# EL-100-020-030-AnalogOUT.net
KiCad netlist of a schematic drawn in EAGLE
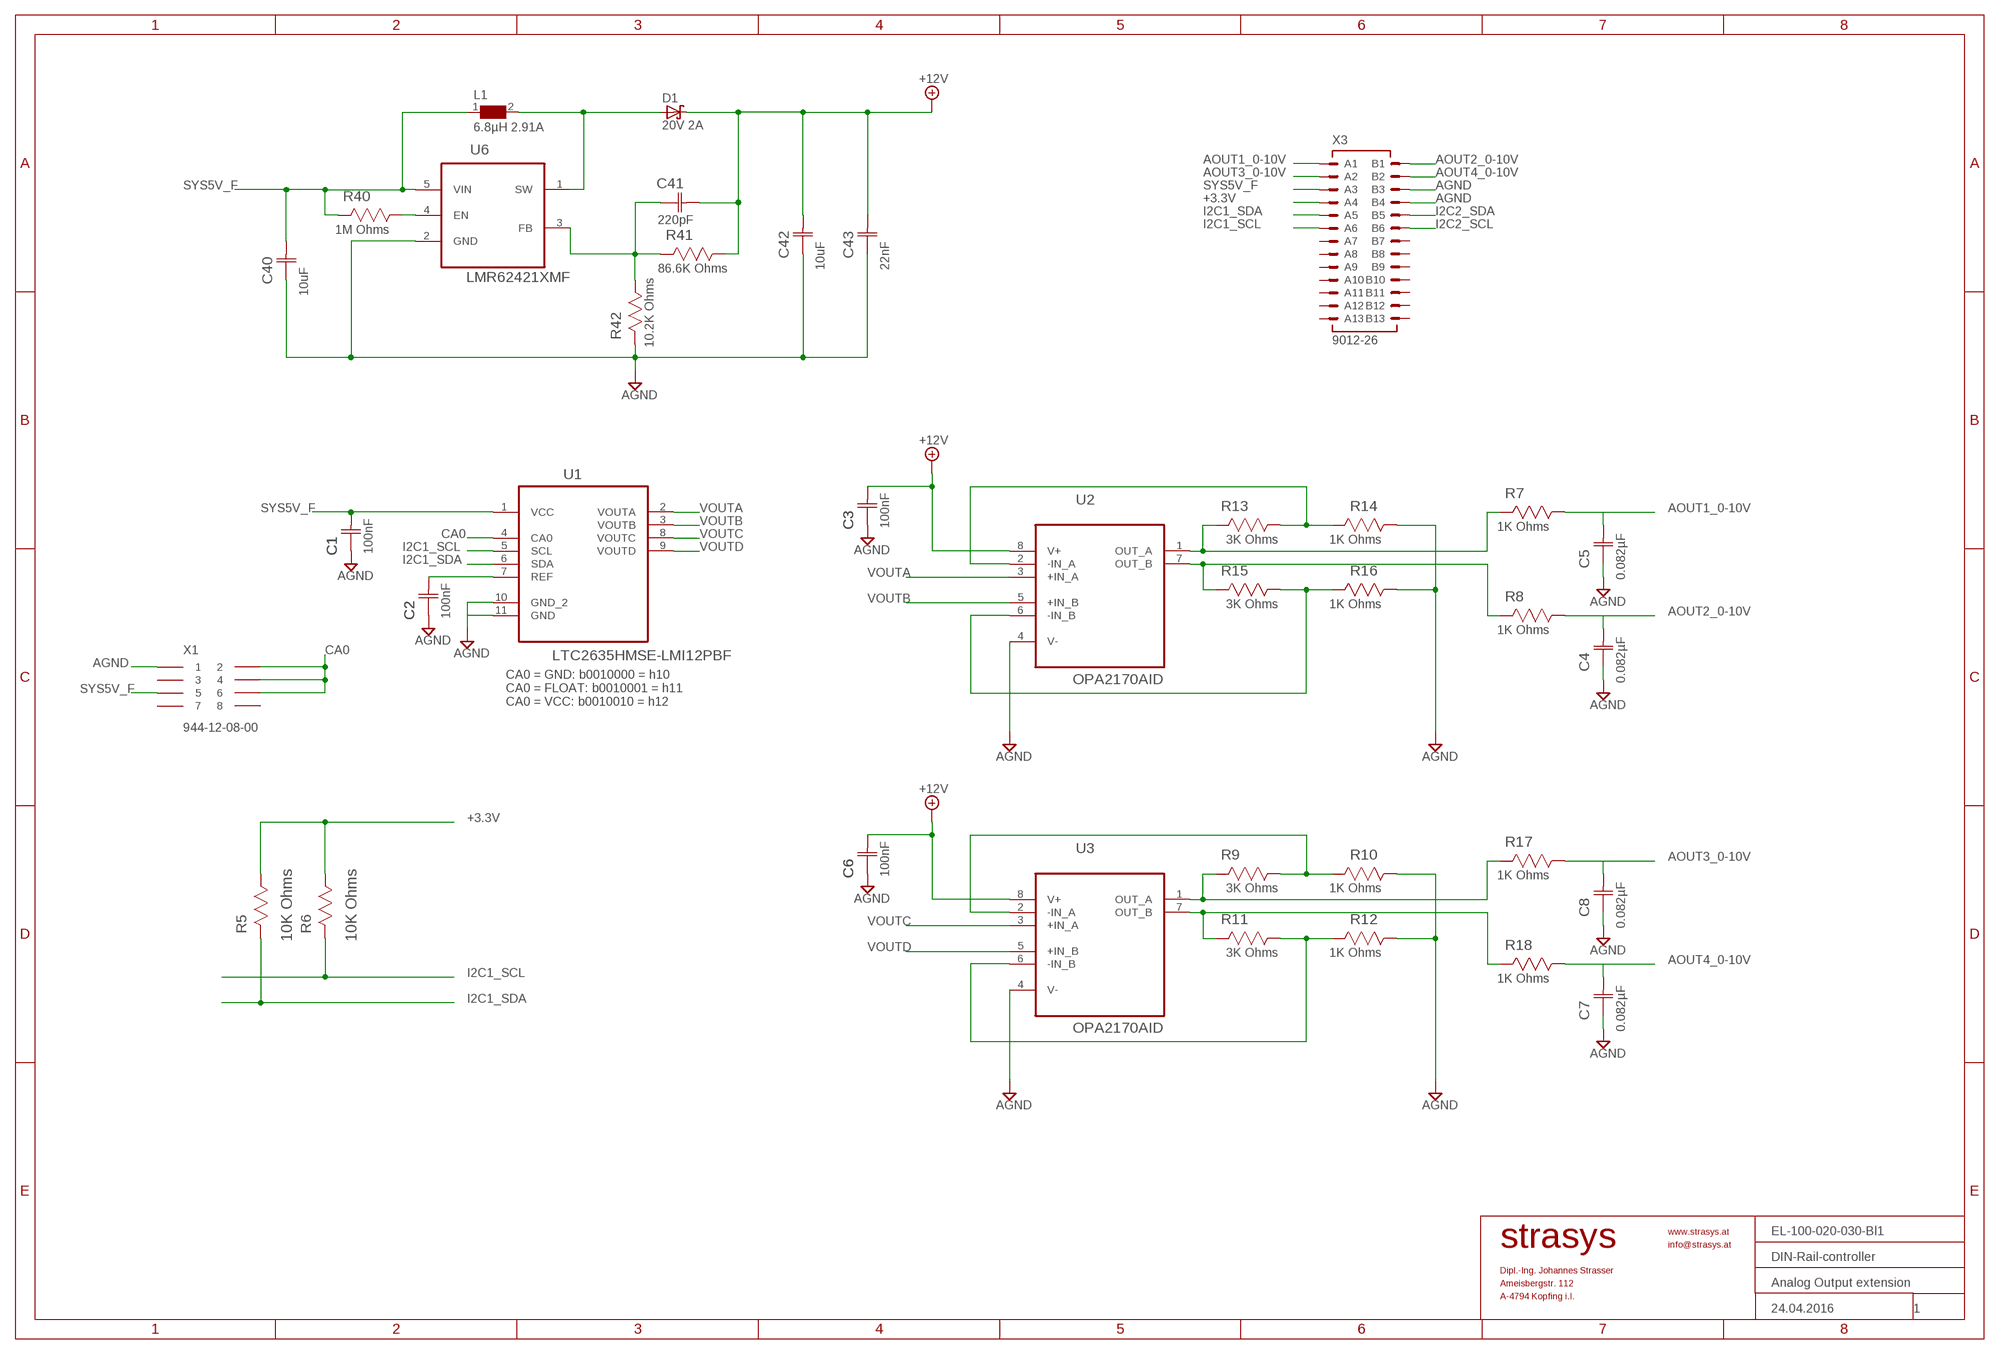
[diagram p0: schematic, sheet 1]
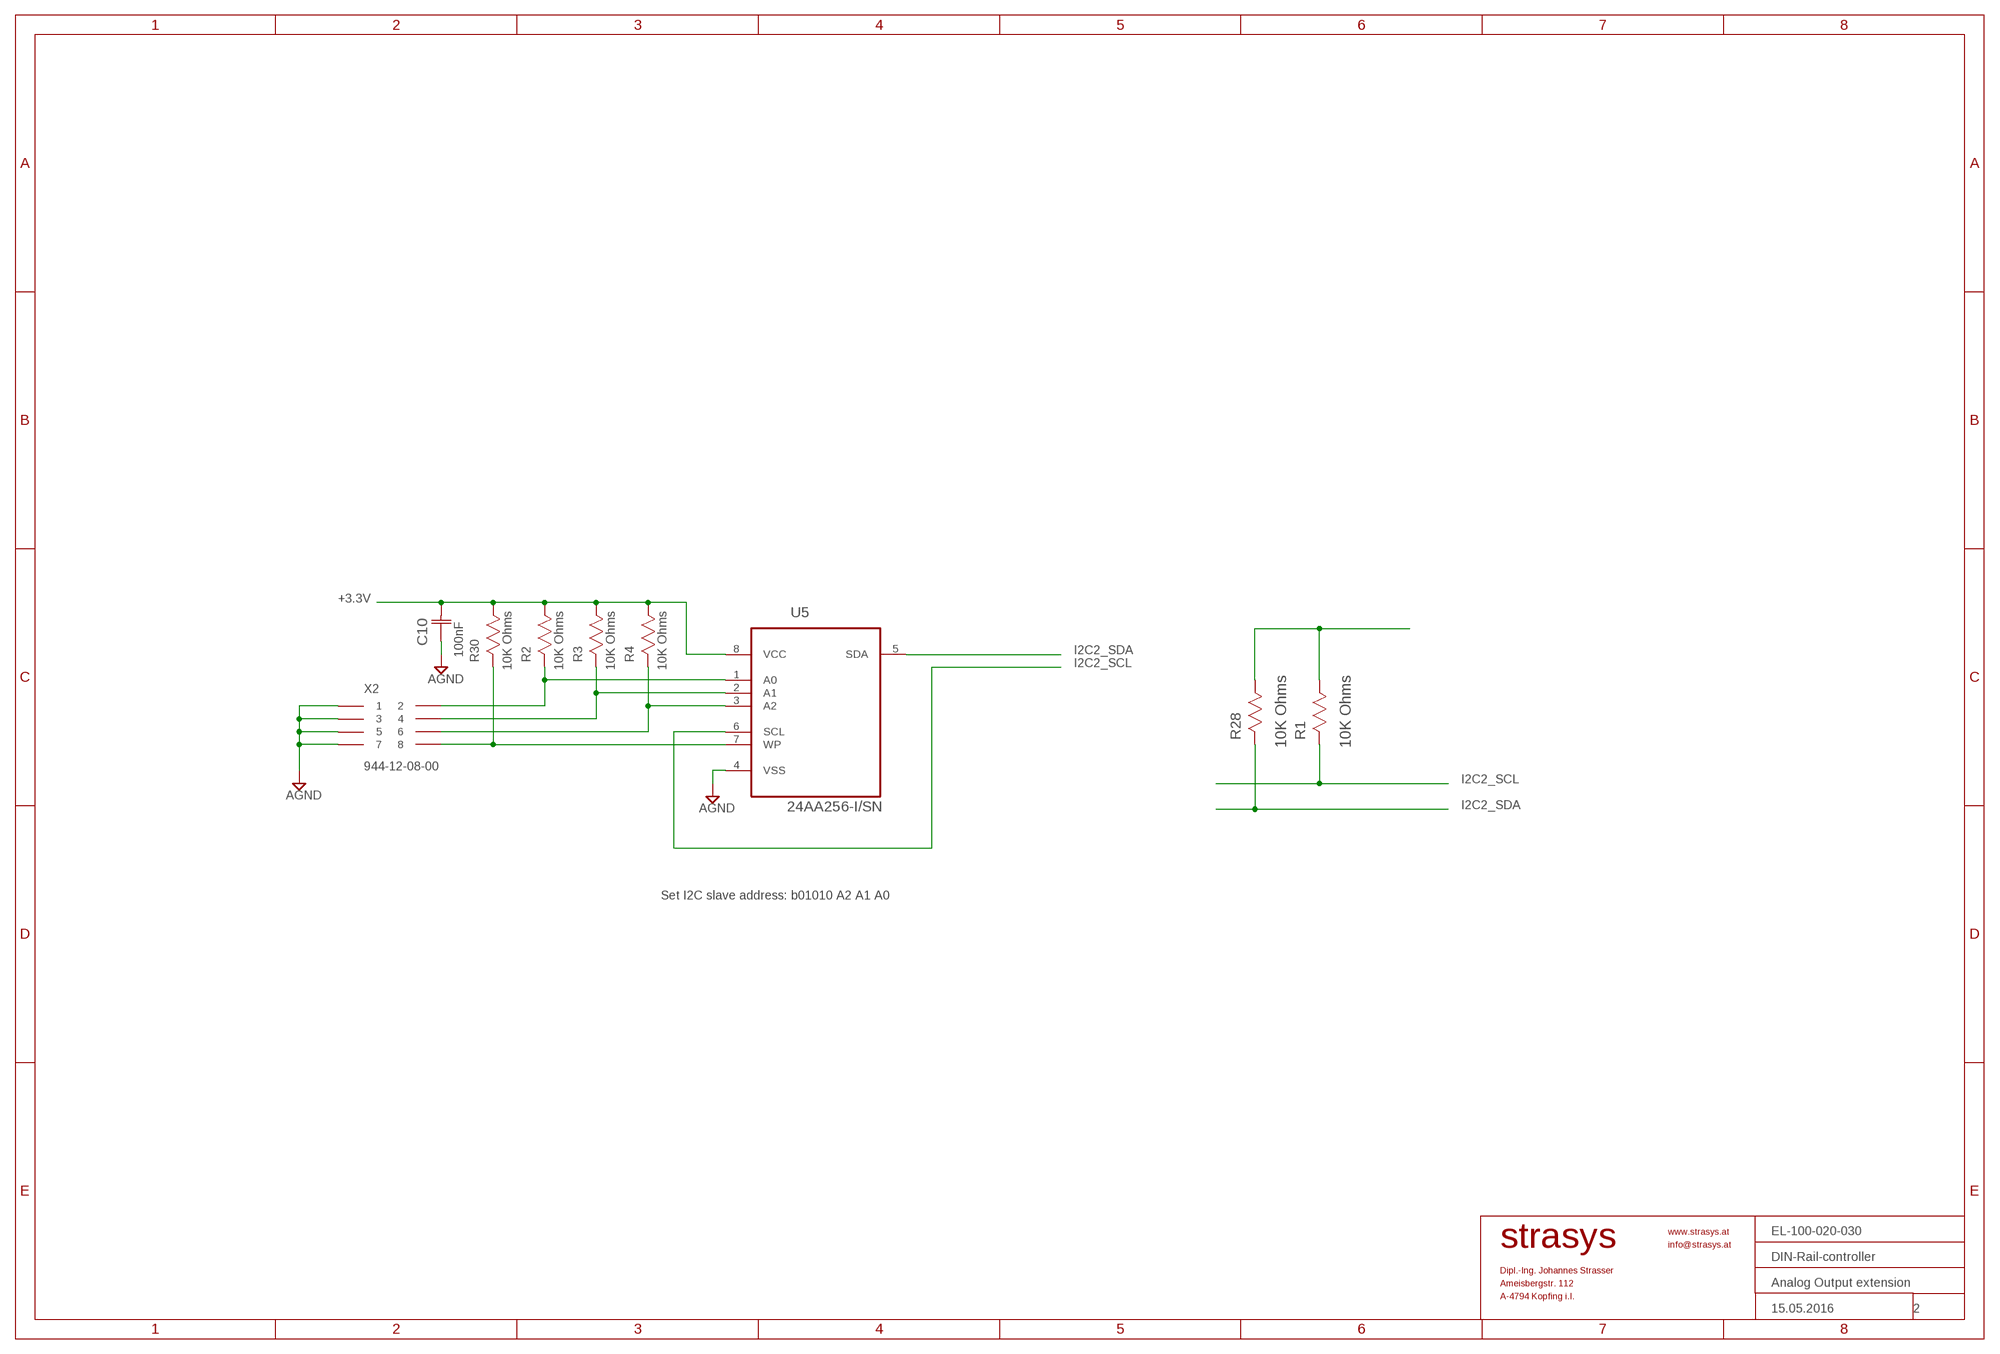
[diagram p1: schematic, sheet 2]

(export (version "E")
  (design (tool "Eeschema 10.0.6"))
  (components
    (comp (ref "C1")
      (value "100nF")
      (footprint "eagle-import:CAPC2013X110N")
      (fields (field (name "MPN") "C0805C104K5RACTU") (field (name "TOLERANCE") "±10%"))
      (libsource (lib "eagle-import") (part "C0805C104K5RACTU"))
    )
    (comp (ref "C2")
      (value "100nF")
      (footprint "eagle-import:CAPC2013X110N")
      (fields (field (name "MPN") "C0805C104K5RACTU") (field (name "TOLERANCE") "±10%"))
      (libsource (lib "eagle-import") (part "C0805C104K5RACTU"))
    )
    (comp (ref "C3")
      (value "100nF")
      (footprint "eagle-import:CAPC2013X110N")
      (fields (field (name "MPN") "C0805C104K5RACTU") (field (name "TOLERANCE") "±10%"))
      (libsource (lib "eagle-import") (part "C0805C104K5RACTU"))
    )
    (comp (ref "C4")
      (value "0.082µF")
      (footprint "eagle-import:CAPC2013X88N")
      (fields
        (field (name "MPN") "C0805C180J5GACTU")
        (field (name "TOLERANCE") "±5%")
        (field (name "MPN_1") "MC0805B823K500CT")
        (field (name "OC_FARNELL") "1759264")
        (field (name "SUPPLIER") "MULTICOMP")
        (field (name "TOLERANCE_1") "±10%")
      )
      (libsource (lib "eagle-import") (part "C0805C180J5GACTU"))
    )
    (comp (ref "C5")
      (value "0.082µF")
      (footprint "eagle-import:CAPC2013X88N")
      (fields
        (field (name "MPN") "C0805C180J5GACTU")
        (field (name "TOLERANCE") "±5%")
        (field (name "MPN_1") "MC0805B823K500CT")
        (field (name "OC_FARNELL") "1759264")
        (field (name "SUPPLIER") "MULTICOMP")
        (field (name "TOLERANCE_1") "±10%")
      )
      (libsource (lib "eagle-import") (part "C0805C180J5GACTU"))
    )
    (comp (ref "C6")
      (value "100nF")
      (footprint "eagle-import:CAPC2013X110N")
      (fields (field (name "MPN") "C0805C104K5RACTU") (field (name "TOLERANCE") "±10%"))
      (libsource (lib "eagle-import") (part "C0805C104K5RACTU"))
    )
    (comp (ref "C7")
      (value "0.082µF")
      (footprint "eagle-import:CAPC2013X88N")
      (fields
        (field (name "MPN") "C0805C180J5GACTU")
        (field (name "TOLERANCE") "±5%")
        (field (name "MPN_1") "MC0805B823K500CT")
        (field (name "OC_FARNELL") "1759264")
        (field (name "SUPPLIER") "MULTICOMP")
        (field (name "TOLERANCE_1") "±10%")
      )
      (libsource (lib "eagle-import") (part "C0805C180J5GACTU"))
    )
    (comp (ref "C8")
      (value "0.082µF")
      (footprint "eagle-import:CAPC2013X88N")
      (fields
        (field (name "MPN") "C0805C180J5GACTU")
        (field (name "TOLERANCE") "±5%")
        (field (name "MPN_1") "MC0805B823K500CT")
        (field (name "OC_FARNELL") "1759264")
        (field (name "SUPPLIER") "MULTICOMP")
        (field (name "TOLERANCE_1") "±10%")
      )
      (libsource (lib "eagle-import") (part "C0805C180J5GACTU"))
    )
    (comp (ref "C40")
      (value "10uF")
      (footprint "eagle-import:CAPC2013X140N")
      (fields
        (field (name "MPN") "C0805C106K8PACTU")
        (field (name "TOLERANCE") "±10%")
        (field (name "MF") "KEMET")
      )
      (libsource (lib "eagle-import") (part "C0805C106K8PACTU"))
    )
    (comp (ref "C41")
      (value "220pF")
      (footprint "eagle-import:CAPC2013X88N")
      (fields
        (field (name "MPN") "C0805C221J5GACTU")
        (field (name "TOLERANCE") "±5%")
        (field (name "MF") "KEMET")
      )
      (libsource (lib "eagle-import") (part "C0805C221J5GACTU"))
    )
    (comp (ref "C42")
      (value "10uF")
      (footprint "eagle-import:CAPC3216X180N")
      (fields
        (field (name "MPN") "C1206C106K3PACTU")
        (field (name "TOLERANCE") "±10%")
        (field (name "MF") "KEMET")
      )
      (libsource (lib "eagle-import") (part "C1206C106K3PACTU"))
    )
    (comp (ref "C43")
      (value "22nF")
      (footprint "eagle-import:CAPC2013X88N")
      (fields
        (field (name "MPN") "C0805C223K5RACTU")
        (field (name "TOLERANCE") "±10%")
        (field (name "MF") "KEMET")
      )
      (libsource (lib "eagle-import") (part "C0805C223K5RACTU"))
    )
    (comp (ref "D1")
      (value "20V 2A")
      (footprint "eagle-import:SMB")
      (fields (field (name "MF") "BOURNS"))
      (libsource (lib "eagle-import") (part "SCHOTTKY-DIODESMD"))
    )
    (comp (ref "L1")
      (value "6.8µH 2.91A")
      (footprint "eagle-import:WE-PD_7332_7345_PLASTIC_BASE")
      (fields (field (name "MPN") "7447779006") (field (name "MF") "WURTH ELEKTRONIK"))
      (libsource (lib "eagle-import") (part "WE-PD_7332/7345_PLASTIC_BASE-7447779006"))
    )
    (comp (ref "R5")
      (value "10K Ohms")
      (footprint "eagle-import:RESC2013X65N")
      (fields
        (field (name "MPN") "CRCW080510K0JNEA")
        (field (name "TOLERANCE") "±5%")
        (field (name "MF") "VISHAY DRALORIC")
      )
      (libsource (lib "eagle-import") (part "CRCW080510K0JNEA"))
    )
    (comp (ref "R6")
      (value "10K Ohms")
      (footprint "eagle-import:RESC2013X65N")
      (fields
        (field (name "MPN") "CRCW080510K0JNEA")
        (field (name "TOLERANCE") "±5%")
        (field (name "MF") "VISHAY DRALORIC")
      )
      (libsource (lib "eagle-import") (part "CRCW080510K0JNEA"))
    )
    (comp (ref "R7")
      (value "1K Ohms")
      (footprint "eagle-import:RESC2013X65N")
      (fields (field (name "MPN") "CRCW08051K00JNEA") (field (name "TOLERANCE") "±5%"))
      (libsource (lib "eagle-import") (part "CRCW08051K00JNEA"))
    )
    (comp (ref "R8")
      (value "1K Ohms")
      (footprint "eagle-import:RESC2013X65N")
      (fields (field (name "MPN") "CRCW08051K00JNEA") (field (name "TOLERANCE") "±5%"))
      (libsource (lib "eagle-import") (part "CRCW08051K00JNEA"))
    )
    (comp (ref "R9")
      (value "3K Ohms")
      (footprint "eagle-import:RESC2013X65N")
      (fields
        (field (name "MPN") "CRCW080530K0FKEA")
        (field (name "TOLERANCE") "±1%")
        (field (name "MPN_1") "ERA6AEB302V")
        (field (name "OC_FARNELL") "1670234")
        (field (name "SUPPLIER") "Panasonic")
        (field (name "TOLERANCE_1") "±0.1%")
      )
      (libsource (lib "eagle-import") (part "CRCW080530K0FKEA"))
    )
    (comp (ref "R10")
      (value "1K Ohms")
      (footprint "eagle-import:RESC2013X65N")
      (fields
        (field (name "MPN") "CRCW08051K00FKEA")
        (field (name "TOLERANCE") "±1%")
        (field (name "MPN_1") "ERA6AEB102V")
        (field (name "OC_FARNELL") "1577659")
        (field (name "SUPPLIER") "PANASONIC")
        (field (name "TOLERANCE_1") "±0.1%")
      )
      (libsource (lib "eagle-import") (part "CRCW08051K00FKEA"))
    )
    (comp (ref "R11")
      (value "3K Ohms")
      (footprint "eagle-import:RESC2013X65N")
      (fields
        (field (name "MPN") "CRCW080530K0FKEA")
        (field (name "TOLERANCE") "±1%")
        (field (name "MPN_1") "ERA6AEB302V")
        (field (name "OC_FARNELL") "1670234")
        (field (name "SUPPLIER") "Panasonic")
        (field (name "TOLERANCE_1") "±0.1%")
      )
      (libsource (lib "eagle-import") (part "CRCW080530K0FKEA"))
    )
    (comp (ref "R12")
      (value "1K Ohms")
      (footprint "eagle-import:RESC2013X65N")
      (fields
        (field (name "MPN") "CRCW08051K00FKEA")
        (field (name "TOLERANCE") "±1%")
        (field (name "MPN_1") "ERA6AEB102V")
        (field (name "OC_FARNELL") "1577659")
        (field (name "SUPPLIER") "PANASONIC")
        (field (name "TOLERANCE_1") "±0.1%")
      )
      (libsource (lib "eagle-import") (part "CRCW08051K00FKEA"))
    )
    (comp (ref "R13")
      (value "3K Ohms")
      (footprint "eagle-import:RESC2013X65N")
      (fields
        (field (name "MPN") "CRCW080530K0FKEA")
        (field (name "TOLERANCE") "±1%")
        (field (name "MPN_1") "ERA6AEB302V")
        (field (name "OC_FARNELL") "1670234")
        (field (name "SUPPLIER") "Panasonic")
        (field (name "TOLERANCE_1") "±0.1%")
      )
      (libsource (lib "eagle-import") (part "CRCW080530K0FKEA"))
    )
    (comp (ref "R14")
      (value "1K Ohms")
      (footprint "eagle-import:RESC2013X65N")
      (fields
        (field (name "MPN") "CRCW08051K00FKEA")
        (field (name "TOLERANCE") "±1%")
        (field (name "MPN_1") "ERA6AEB102V")
        (field (name "OC_FARNELL") "1577659")
        (field (name "SUPPLIER") "PANASONIC")
        (field (name "TOLERANCE_1") "±0.1%")
      )
      (libsource (lib "eagle-import") (part "CRCW08051K00FKEA"))
    )
    (comp (ref "R15")
      (value "3K Ohms")
      (footprint "eagle-import:RESC2013X65N")
      (fields
        (field (name "MPN") "CRCW080530K0FKEA")
        (field (name "TOLERANCE") "±1%")
        (field (name "MPN_1") "ERA6AEB302V")
        (field (name "OC_FARNELL") "1670234")
        (field (name "SUPPLIER") "Panasonic")
        (field (name "TOLERANCE_1") "±0.1%")
      )
      (libsource (lib "eagle-import") (part "CRCW080530K0FKEA"))
    )
    (comp (ref "R16")
      (value "1K Ohms")
      (footprint "eagle-import:RESC2013X65N")
      (fields
        (field (name "MPN") "CRCW08051K00FKEA")
        (field (name "TOLERANCE") "±1%")
        (field (name "MPN_1") "ERA6AEB102V")
        (field (name "OC_FARNELL") "1577659")
        (field (name "SUPPLIER") "PANASONIC")
        (field (name "TOLERANCE_1") "±0.1%")
      )
      (libsource (lib "eagle-import") (part "CRCW08051K00FKEA"))
    )
    (comp (ref "R17")
      (value "1K Ohms")
      (footprint "eagle-import:RESC2013X65N")
      (fields (field (name "MPN") "CRCW08051K00JNEA") (field (name "TOLERANCE") "±5%"))
      (libsource (lib "eagle-import") (part "CRCW08051K00JNEA"))
    )
    (comp (ref "R18")
      (value "1K Ohms")
      (footprint "eagle-import:RESC2013X65N")
      (fields (field (name "MPN") "CRCW08051K00JNEA") (field (name "TOLERANCE") "±5%"))
      (libsource (lib "eagle-import") (part "CRCW08051K00JNEA"))
    )
    (comp (ref "R40")
      (value "1M Ohms")
      (footprint "eagle-import:RESC2013X65N")
      (fields
        (field (name "MPN") "CRCW08051M00FKTB")
        (field (name "TOLERANCE") "±1%")
        (field (name "MF") "VISHAY DRALORIC")
      )
      (libsource (lib "eagle-import") (part "CRCW08051M00FKTB"))
    )
    (comp (ref "R41")
      (value "86.6K Ohms")
      (footprint "eagle-import:RESC2013X65N")
      (fields
        (field (name "MPN") "CRCW080586K6FKEA")
        (field (name "TOLERANCE") "±1%")
        (field (name "MF") "VISHAY DRALORIC")
      )
      (libsource (lib "eagle-import") (part "CRCW080586K6FKEA"))
    )
    (comp (ref "R42")
      (value "10.2K Ohms")
      (footprint "eagle-import:RESC2013X65N")
      (fields
        (field (name "MPN") "CRCW080510K2FKEA")
        (field (name "TOLERANCE") "±1%")
        (field (name "MF") "VISHAY DRALORIC")
      )
      (libsource (lib "eagle-import") (part "CRCW080510K2FKEA"))
    )
    (comp (ref "U1")
      (value "LTC2635HMSE-LMI12PBF")
      (footprint "eagle-import:SOP50P490X110-11N")
      (fields (field (name "MPN") "LTC2635HMSE-LMI12#PBF"))
      (libsource (lib "eagle-import") (part "LTC2635HMSE-LMI12PBF"))
    )
    (comp (ref "U2")
      (value "OPA2170AID")
      (footprint "eagle-import:SOIC127P600X175-8N")
      (fields (field (name "MF") "TEXAS INSTRUMENTS"))
      (libsource (lib "eagle-import") (part "OPA2170AID"))
    )
    (comp (ref "U3")
      (value "OPA2170AID")
      (footprint "eagle-import:SOIC127P600X175-8N")
      (fields (field (name "MF") "TEXAS INSTRUMENTS"))
      (libsource (lib "eagle-import") (part "OPA2170AID"))
    )
    (comp (ref "U6")
      (value "LMR62421XMF")
      (footprint "eagle-import:SOT95P290X145-5N")
      (libsource (lib "eagle-import") (part "LMR62421XMF"))
    )
    (comp (ref "X1")
      (value "944-12-08-00")
      (footprint "eagle-import:2,54_2X8")
      (libsource (lib "eagle-import") (part "944-12-08-00"))
    )
    (comp (ref "X3")
      (value "9012-26")
      (footprint "eagle-import:9012-26")
      (libsource (lib "eagle-import") (part "9012-26"))
    )
    (comp (ref "C10")
      (value "100nF")
      (footprint "eagle-import:CAPC2013X110N")
      (fields
        (field (name "MPN") "C0805C104K5RACTU")
        (field (name "TOLERANCE") "±10%")
        (field (name "MF") "KEMET")
      )
      (libsource (lib "eagle-import") (part "C0805C104K5RACTU"))
    )
    (comp (ref "R1")
      (value "10K Ohms")
      (footprint "eagle-import:RESC2013X65N")
      (fields
        (field (name "MPN") "CRCW080510K0JNEA")
        (field (name "TOLERANCE") "±5%")
        (field (name "MF") "VISHAY DRALORIC")
      )
      (libsource (lib "eagle-import") (part "CRCW080510K0JNEA"))
    )
    (comp (ref "R2")
      (value "10K Ohms")
      (footprint "eagle-import:RESC2013X65N")
      (fields
        (field (name "MPN") "CRCW080510K0JNEA")
        (field (name "TOLERANCE") "±5%")
        (field (name "MF") "VISHAY DRALORIC")
      )
      (libsource (lib "eagle-import") (part "CRCW080510K0JNEA"))
    )
    (comp (ref "R3")
      (value "10K Ohms")
      (footprint "eagle-import:RESC2013X65N")
      (fields
        (field (name "MPN") "CRCW080510K0JNEA")
        (field (name "TOLERANCE") "±5%")
        (field (name "MF") "VISHAY DRALORIC")
      )
      (libsource (lib "eagle-import") (part "CRCW080510K0JNEA"))
    )
    (comp (ref "R4")
      (value "10K Ohms")
      (footprint "eagle-import:RESC2013X65N")
      (fields
        (field (name "MPN") "CRCW080510K0JNEA")
        (field (name "TOLERANCE") "±5%")
        (field (name "MF") "VISHAY DRALORIC")
      )
      (libsource (lib "eagle-import") (part "CRCW080510K0JNEA"))
    )
    (comp (ref "R28")
      (value "10K Ohms")
      (footprint "eagle-import:RESC2013X65N")
      (fields
        (field (name "MPN") "CRCW080510K0JNEA")
        (field (name "TOLERANCE") "±5%")
        (field (name "MF") "VISHAY DRALORIC")
      )
      (libsource (lib "eagle-import") (part "CRCW080510K0JNEA"))
    )
    (comp (ref "R30")
      (value "10K Ohms")
      (footprint "eagle-import:RESC2013X65N")
      (fields
        (field (name "MPN") "CRCW080510K0JNEA")
        (field (name "TOLERANCE") "±5%")
        (field (name "MF") "VISHAY DRALORIC")
      )
      (libsource (lib "eagle-import") (part "CRCW080510K0JNEA"))
    )
    (comp (ref "U5")
      (value "24AA256-I/SN")
      (footprint "eagle-import:SOIC127P600X175-8N")
      (fields (field (name "MF") "MICROCHIP"))
      (libsource (lib "eagle-import") (part "24AA256-I/SN"))
    )
    (comp (ref "X2")
      (value "944-12-08-00")
      (footprint "eagle-import:2,54_2X8")
      (libsource (lib "eagle-import") (part "944-12-08-00"))
    )
  )
  (nets
    (net (code "1") (name "+3.3V") (class "Default")
      (node (ref "C10") (pin "2") (pinfunction "C2_2") (pintype "passive"))
      (node (ref "R1") (pin "1") (pinfunction "1_1") (pintype "passive"))
      (node (ref "R2") (pin "1") (pinfunction "1_1") (pintype "passive"))
      (node (ref "R28") (pin "1") (pinfunction "1_1") (pintype "passive"))
      (node (ref "R3") (pin "1") (pinfunction "1_1") (pintype "passive"))
      (node (ref "R30") (pin "1") (pinfunction "1_1") (pintype "passive"))
      (node (ref "R4") (pin "1") (pinfunction "1_1") (pintype "passive"))
      (node (ref "R5") (pin "1") (pinfunction "1_1") (pintype "passive"))
      (node (ref "R6") (pin "1") (pinfunction "1_1") (pintype "passive"))
      (node (ref "U5") (pin "8") (pinfunction "VCC_8") (pintype "power_in"))
      (node (ref "X3") (pin "A4") (pinfunction "A4_A4") (pintype "passive"))
    )
    (net (code "2") (name "+12V") (class "Default")
      (node (ref "C3") (pin "2") (pinfunction "C2_2") (pintype "passive"))
      (node (ref "C41") (pin "2") (pinfunction "C2_2") (pintype "passive"))
      (node (ref "C42") (pin "2") (pinfunction "C2_2") (pintype "passive"))
      (node (ref "C43") (pin "2") (pinfunction "C2_2") (pintype "passive"))
      (node (ref "C6") (pin "2") (pinfunction "C2_2") (pintype "passive"))
      (node (ref "D1") (pin "C") (pinfunction "C_C") (pintype "passive"))
      (node (ref "R41") (pin "1") (pinfunction "1_1") (pintype "passive"))
      (node (ref "U2") (pin "8") (pinfunction "V+_8") (pintype "power_in"))
      (node (ref "U3") (pin "8") (pinfunction "V+_8") (pintype "power_in"))
    )
    (net (code "3") (name "AGND") (class "Default")
      (node (ref "C1") (pin "1") (pinfunction "C1_1") (pintype "passive"))
      (node (ref "C10") (pin "1") (pinfunction "C1_1") (pintype "passive"))
      (node (ref "C2") (pin "1") (pinfunction "C1_1") (pintype "passive"))
      (node (ref "C3") (pin "1") (pinfunction "C1_1") (pintype "passive"))
      (node (ref "C4") (pin "1") (pinfunction "C1_1") (pintype "passive"))
      (node (ref "C40") (pin "1") (pinfunction "C1_1") (pintype "passive"))
      (node (ref "C42") (pin "1") (pinfunction "C1_1") (pintype "passive"))
      (node (ref "C43") (pin "1") (pinfunction "C1_1") (pintype "passive"))
      (node (ref "C5") (pin "1") (pinfunction "C1_1") (pintype "passive"))
      (node (ref "C6") (pin "1") (pinfunction "C1_1") (pintype "passive"))
      (node (ref "C7") (pin "1") (pinfunction "C1_1") (pintype "passive"))
      (node (ref "C8") (pin "1") (pinfunction "C1_1") (pintype "passive"))
      (node (ref "R10") (pin "1") (pinfunction "1_1") (pintype "passive"))
      (node (ref "R12") (pin "1") (pinfunction "1_1") (pintype "passive"))
      (node (ref "R14") (pin "1") (pinfunction "1_1") (pintype "passive"))
      (node (ref "R16") (pin "1") (pinfunction "1_1") (pintype "passive"))
      (node (ref "R42") (pin "2") (pinfunction "2_2") (pintype "passive"))
      (node (ref "U1") (pin "10") (pinfunction "GND_2_10") (pintype "passive"))
      (node (ref "U1") (pin "11") (pinfunction "GND_11") (pintype "passive"))
      (node (ref "U2") (pin "4") (pinfunction "V-_4") (pintype "passive"))
      (node (ref "U3") (pin "4") (pinfunction "V-_4") (pintype "passive"))
      (node (ref "U5") (pin "4") (pinfunction "VSS_4") (pintype "passive"))
      (node (ref "U6") (pin "2") (pinfunction "GND_2") (pintype "passive"))
      (node (ref "X1") (pin "P1") (pinfunction "1_P1") (pintype "bidirectional"))
      (node (ref "X2") (pin "P1") (pinfunction "1_P1") (pintype "bidirectional"))
      (node (ref "X2") (pin "P3") (pinfunction "3_P3") (pintype "bidirectional"))
      (node (ref "X2") (pin "P5") (pinfunction "5_P5") (pintype "bidirectional"))
      (node (ref "X2") (pin "P7") (pinfunction "7_P7") (pintype "bidirectional"))
      (node (ref "X3") (pin "B3") (pinfunction "B3_B3") (pintype "passive"))
      (node (ref "X3") (pin "B4") (pinfunction "B4_B4") (pintype "passive"))
    )
    (net (code "4") (name "AOUT1_0-10V") (class "Default")
      (node (ref "C5") (pin "2") (pinfunction "C2_2") (pintype "passive"))
      (node (ref "R7") (pin "1") (pinfunction "1_1") (pintype "passive"))
      (node (ref "X3") (pin "A1") (pinfunction "A1_A1") (pintype "passive"))
    )
    (net (code "5") (name "AOUT2_0-10V") (class "Default")
      (node (ref "C4") (pin "2") (pinfunction "C2_2") (pintype "passive"))
      (node (ref "R8") (pin "1") (pinfunction "1_1") (pintype "passive"))
      (node (ref "X3") (pin "B1") (pinfunction "B1_B1") (pintype "passive"))
    )
    (net (code "6") (name "AOUT3_0-10V") (class "Default")
      (node (ref "C8") (pin "2") (pinfunction "C2_2") (pintype "passive"))
      (node (ref "R17") (pin "1") (pinfunction "1_1") (pintype "passive"))
      (node (ref "X3") (pin "A2") (pinfunction "A2_A2") (pintype "passive"))
    )
    (net (code "7") (name "AOUT4_0-10V") (class "Default")
      (node (ref "C7") (pin "2") (pinfunction "C2_2") (pintype "passive"))
      (node (ref "R18") (pin "1") (pinfunction "1_1") (pintype "passive"))
      (node (ref "X3") (pin "B2") (pinfunction "B2_B2") (pintype "passive"))
    )
    (net (code "8") (name "CA0") (class "Default")
      (node (ref "U1") (pin "4") (pinfunction "CA0_4") (pintype "input"))
      (node (ref "X1") (pin "P2") (pinfunction "2_P2") (pintype "bidirectional"))
      (node (ref "X1") (pin "P4") (pinfunction "4_P4") (pintype "bidirectional"))
      (node (ref "X1") (pin "P6") (pinfunction "6_P6") (pintype "bidirectional"))
    )
    (net (code "9") (name "I2C1_SCL") (class "Default")
      (node (ref "R6") (pin "2") (pinfunction "2_2") (pintype "passive"))
      (node (ref "U1") (pin "5") (pinfunction "SCL_5") (pintype "input"))
      (node (ref "X3") (pin "A6") (pinfunction "A6_A6") (pintype "passive"))
    )
    (net (code "10") (name "I2C1_SDA") (class "Default")
      (node (ref "R5") (pin "2") (pinfunction "2_2") (pintype "passive"))
      (node (ref "U1") (pin "6") (pinfunction "SDA_6") (pintype "bidirectional"))
      (node (ref "X3") (pin "A5") (pinfunction "A5_A5") (pintype "passive"))
    )
    (net (code "11") (name "I2C2_SCL") (class "Default")
      (node (ref "R1") (pin "2") (pinfunction "2_2") (pintype "passive"))
      (node (ref "U5") (pin "6") (pinfunction "SCL_6") (pintype "input"))
      (node (ref "X3") (pin "B6") (pinfunction "B6_B6") (pintype "passive"))
    )
    (net (code "12") (name "I2C2_SDA") (class "Default")
      (node (ref "R28") (pin "2") (pinfunction "2_2") (pintype "passive"))
      (node (ref "U5") (pin "5") (pinfunction "SDA_5") (pintype "bidirectional"))
      (node (ref "X3") (pin "B5") (pinfunction "B5_B5") (pintype "passive"))
    )
    (net (code "13") (name "Net-(C2-C2)") (class "Default")
      (node (ref "C2") (pin "2") (pinfunction "C2_2") (pintype "passive"))
      (node (ref "U1") (pin "7") (pinfunction "REF_7") (pintype "bidirectional"))
    )
    (net (code "14") (name "Net-(C41-C1)") (class "Default")
      (node (ref "C41") (pin "1") (pinfunction "C1_1") (pintype "passive"))
      (node (ref "R41") (pin "2") (pinfunction "2_2") (pintype "passive"))
      (node (ref "R42") (pin "1") (pinfunction "1_1") (pintype "passive"))
      (node (ref "U6") (pin "3") (pinfunction "FB_3") (pintype "input"))
    )
    (net (code "15") (name "Net-(U2--IN_A)") (class "Default")
      (node (ref "R13") (pin "1") (pinfunction "1_1") (pintype "passive"))
      (node (ref "R14") (pin "2") (pinfunction "2_2") (pintype "passive"))
      (node (ref "U2") (pin "2") (pinfunction "-IN_A_2") (pintype "input"))
    )
    (net (code "16") (name "Net-(U2--IN_B)") (class "Default")
      (node (ref "R15") (pin "1") (pinfunction "1_1") (pintype "passive"))
      (node (ref "R16") (pin "2") (pinfunction "2_2") (pintype "passive"))
      (node (ref "U2") (pin "6") (pinfunction "-IN_B_6") (pintype "input"))
    )
    (net (code "17") (name "Net-(U2-OUT_A)") (class "Default")
      (node (ref "R13") (pin "2") (pinfunction "2_2") (pintype "passive"))
      (node (ref "R7") (pin "2") (pinfunction "2_2") (pintype "passive"))
      (node (ref "U2") (pin "1") (pinfunction "OUT_A_1") (pintype "output"))
    )
    (net (code "18") (name "Net-(U2-OUT_B)") (class "Default")
      (node (ref "R15") (pin "2") (pinfunction "2_2") (pintype "passive"))
      (node (ref "R8") (pin "2") (pinfunction "2_2") (pintype "passive"))
      (node (ref "U2") (pin "7") (pinfunction "OUT_B_7") (pintype "output"))
    )
    (net (code "19") (name "Net-(U3--IN_A)") (class "Default")
      (node (ref "R10") (pin "2") (pinfunction "2_2") (pintype "passive"))
      (node (ref "R9") (pin "1") (pinfunction "1_1") (pintype "passive"))
      (node (ref "U3") (pin "2") (pinfunction "-IN_A_2") (pintype "input"))
    )
    (net (code "20") (name "Net-(U3--IN_B)") (class "Default")
      (node (ref "R11") (pin "1") (pinfunction "1_1") (pintype "passive"))
      (node (ref "R12") (pin "2") (pinfunction "2_2") (pintype "passive"))
      (node (ref "U3") (pin "6") (pinfunction "-IN_B_6") (pintype "input"))
    )
    (net (code "21") (name "Net-(U3-OUT_A)") (class "Default")
      (node (ref "R17") (pin "2") (pinfunction "2_2") (pintype "passive"))
      (node (ref "R9") (pin "2") (pinfunction "2_2") (pintype "passive"))
      (node (ref "U3") (pin "1") (pinfunction "OUT_A_1") (pintype "output"))
    )
    (net (code "22") (name "Net-(U3-OUT_B)") (class "Default")
      (node (ref "R11") (pin "2") (pinfunction "2_2") (pintype "passive"))
      (node (ref "R18") (pin "2") (pinfunction "2_2") (pintype "passive"))
      (node (ref "U3") (pin "7") (pinfunction "OUT_B_7") (pintype "output"))
    )
    (net (code "23") (name "Net-(U5-A0)") (class "Default")
      (node (ref "R2") (pin "2") (pinfunction "2_2") (pintype "passive"))
      (node (ref "U5") (pin "1") (pinfunction "A0_1") (pintype "input"))
      (node (ref "X2") (pin "P2") (pinfunction "2_P2") (pintype "bidirectional"))
    )
    (net (code "24") (name "Net-(U5-A1)") (class "Default")
      (node (ref "R3") (pin "2") (pinfunction "2_2") (pintype "passive"))
      (node (ref "U5") (pin "2") (pinfunction "A1_2") (pintype "input"))
      (node (ref "X2") (pin "P4") (pinfunction "4_P4") (pintype "bidirectional"))
    )
    (net (code "25") (name "Net-(U5-A2)") (class "Default")
      (node (ref "R4") (pin "2") (pinfunction "2_2") (pintype "passive"))
      (node (ref "U5") (pin "3") (pinfunction "A2_3") (pintype "input"))
      (node (ref "X2") (pin "P6") (pinfunction "6_P6") (pintype "bidirectional"))
    )
    (net (code "26") (name "Net-(U5-WP)") (class "Default")
      (node (ref "R30") (pin "2") (pinfunction "2_2") (pintype "passive"))
      (node (ref "U5") (pin "7") (pinfunction "WP_7") (pintype "input"))
      (node (ref "X2") (pin "P8") (pinfunction "8_P8") (pintype "bidirectional"))
    )
    (net (code "27") (name "Net-(U6-EN)") (class "Default")
      (node (ref "R40") (pin "1") (pinfunction "1_1") (pintype "passive"))
      (node (ref "U6") (pin "4") (pinfunction "EN_4") (pintype "input"))
    )
    (net (code "28") (name "Net-(U6-SW)") (class "Default")
      (node (ref "D1") (pin "A") (pinfunction "A_A") (pintype "passive"))
      (node (ref "L1") (pin "2") (pinfunction "2_2") (pintype "passive"))
      (node (ref "U6") (pin "1") (pinfunction "SW_1") (pintype "passive"))
    )
    (net (code "29") (name "SYS5V_F") (class "Default")
      (node (ref "C1") (pin "2") (pinfunction "C2_2") (pintype "passive"))
      (node (ref "C40") (pin "2") (pinfunction "C2_2") (pintype "passive"))
      (node (ref "L1") (pin "1") (pinfunction "1_1") (pintype "passive"))
      (node (ref "R40") (pin "2") (pinfunction "2_2") (pintype "passive"))
      (node (ref "U1") (pin "1") (pinfunction "VCC_1") (pintype "power_in"))
      (node (ref "U6") (pin "5") (pinfunction "VIN_5") (pintype "power_in"))
      (node (ref "X1") (pin "P5") (pinfunction "5_P5") (pintype "bidirectional"))
      (node (ref "X3") (pin "A3") (pinfunction "A3_A3") (pintype "passive"))
    )
    (net (code "30") (name "VOUTA") (class "Default")
      (node (ref "U1") (pin "2") (pinfunction "VOUTA_2") (pintype "output"))
      (node (ref "U2") (pin "3") (pinfunction "+IN_A_3") (pintype "input"))
    )
    (net (code "31") (name "VOUTB") (class "Default")
      (node (ref "U1") (pin "3") (pinfunction "VOUTB_3") (pintype "output"))
      (node (ref "U2") (pin "5") (pinfunction "+IN_B_5") (pintype "input"))
    )
    (net (code "32") (name "VOUTC") (class "Default")
      (node (ref "U1") (pin "8") (pinfunction "VOUTC_8") (pintype "output"))
      (node (ref "U3") (pin "3") (pinfunction "+IN_A_3") (pintype "input"))
    )
    (net (code "33") (name "VOUTD") (class "Default")
      (node (ref "U1") (pin "9") (pinfunction "VOUTD_9") (pintype "output"))
      (node (ref "U3") (pin "5") (pinfunction "+IN_B_5") (pintype "input"))
    )
    (net (code "34") (name "unconnected-(X1-3-PadP3)") (class "Default")
      (node (ref "X1") (pin "P3") (pinfunction "3_P3") (pintype "bidirectional"))
    )
    (net (code "35") (name "unconnected-(X1-7-PadP7)") (class "Default")
      (node (ref "X1") (pin "P7") (pinfunction "7_P7") (pintype "bidirectional"))
    )
    (net (code "36") (name "unconnected-(X1-8-PadP8)") (class "Default")
      (node (ref "X1") (pin "P8") (pinfunction "8_P8") (pintype "bidirectional"))
    )
    (net (code "37") (name "unconnected-(X3-PadA7)") (class "Default")
      (node (ref "X3") (pin "A7") (pinfunction "A7_A7") (pintype "passive"))
    )
    (net (code "38") (name "unconnected-(X3-PadA8)") (class "Default")
      (node (ref "X3") (pin "A8") (pinfunction "A8_A8") (pintype "passive"))
    )
    (net (code "39") (name "unconnected-(X3-PadA9)") (class "Default")
      (node (ref "X3") (pin "A9") (pinfunction "A9_A9") (pintype "passive"))
    )
    (net (code "40") (name "unconnected-(X3-PadA10)") (class "Default")
      (node (ref "X3") (pin "A10") (pinfunction "A10_A10") (pintype "passive"))
    )
    (net (code "41") (name "unconnected-(X3-PadA11)") (class "Default")
      (node (ref "X3") (pin "A11") (pinfunction "A11_A11") (pintype "passive"))
    )
    (net (code "42") (name "unconnected-(X3-PadA12)") (class "Default")
      (node (ref "X3") (pin "A12") (pinfunction "A12_A12") (pintype "passive"))
    )
    (net (code "43") (name "unconnected-(X3-PadA13)") (class "Default")
      (node (ref "X3") (pin "A13") (pinfunction "A13_A13") (pintype "passive"))
    )
    (net (code "44") (name "unconnected-(X3-PadB7)") (class "Default")
      (node (ref "X3") (pin "B7") (pinfunction "B7_B7") (pintype "passive"))
    )
    (net (code "45") (name "unconnected-(X3-PadB8)") (class "Default")
      (node (ref "X3") (pin "B8") (pinfunction "B8_B8") (pintype "passive"))
    )
    (net (code "46") (name "unconnected-(X3-PadB9)") (class "Default")
      (node (ref "X3") (pin "B9") (pinfunction "B9_B9") (pintype "passive"))
    )
    (net (code "47") (name "unconnected-(X3-PadB10)") (class "Default")
      (node (ref "X3") (pin "B10") (pinfunction "B10_B10") (pintype "passive"))
    )
    (net (code "48") (name "unconnected-(X3-PadB11)") (class "Default")
      (node (ref "X3") (pin "B11") (pinfunction "B11_B11") (pintype "passive"))
    )
    (net (code "49") (name "unconnected-(X3-PadB12)") (class "Default")
      (node (ref "X3") (pin "B12") (pinfunction "B12_B12") (pintype "passive"))
    )
    (net (code "50") (name "unconnected-(X3-PadB13)") (class "Default")
      (node (ref "X3") (pin "B13") (pinfunction "B13_B13") (pintype "passive"))
    )
  )
)
